# USB.net
KiCad netlist of a schematic drawn in Altium Designer
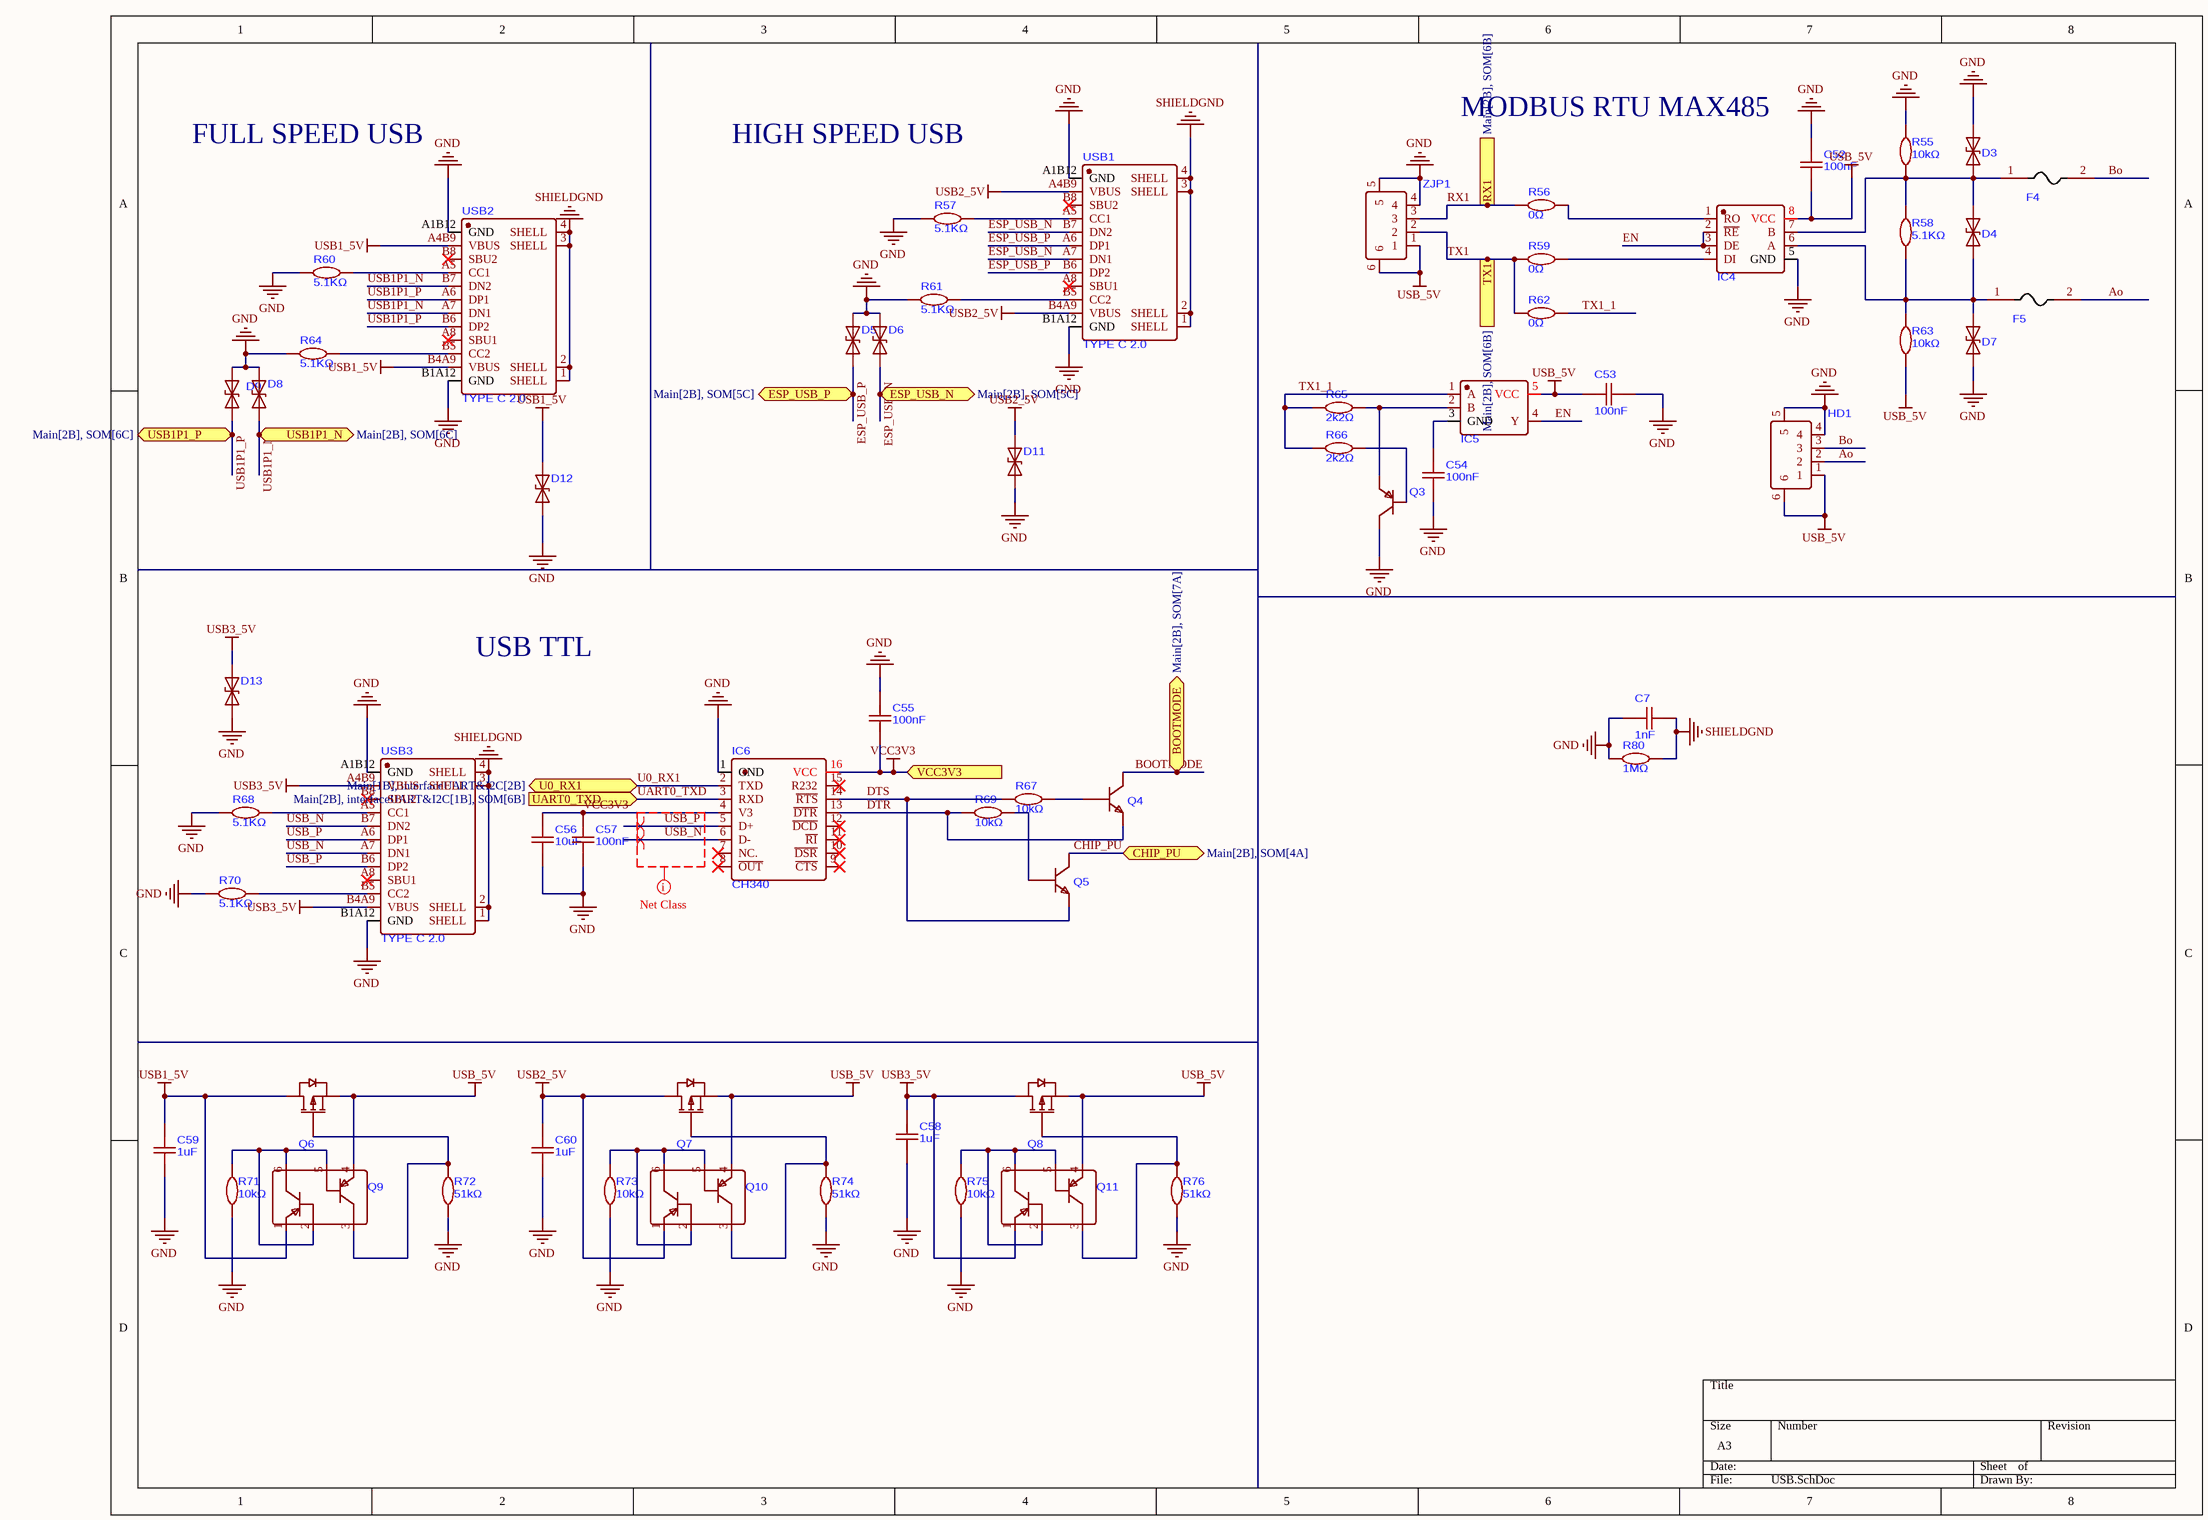
[diagram p0: USB.SchDoc]

(export (version "E")
  (design (tool "Eeschema 10.0.6"))
  (components
    (comp (ref "C7")
      (value "1nF")
      (footprint "C1808")
      (description "50V 1nF X7R ±10% 0603 Ceramic Capacitors ROHS")
      (libsource (lib "Schlib2") (part "CL10B102KB8NNNC"))
    )
    (comp (ref "C52")
      (value "100nF")
      (footprint "C0603")
      (description "50V 100nF X7R ±10% 0603 Ceramic Capacitors ROHS")
      (libsource (lib "Schlib2") (part "CC0603KRX7R9BB104"))
    )
    (comp (ref "C53")
      (value "100nF")
      (footprint "C0603")
      (description "50V 100nF X7R ±10% 0603 Ceramic Capacitors ROHS")
      (libsource (lib "Schlib2") (part "CC0603KRX7R9BB104"))
    )
    (comp (ref "C54")
      (value "100nF")
      (footprint "C0603")
      (description "50V 100nF X7R ±10% 0603 Ceramic Capacitors ROHS")
      (libsource (lib "Schlib2") (part "CC0603KRX7R9BB104"))
    )
    (comp (ref "C55")
      (value "100nF")
      (footprint "C0603")
      (description "50V 100nF X7R ±10% 0603 Ceramic Capacitors ROHS")
      (libsource (lib "Schlib2") (part "CC0603KRX7R9BB104"))
    )
    (comp (ref "C56")
      (value "10uF")
      (footprint "C0603")
      (description "25V 10uF X5R ±20% 0603 Ceramic Capacitors ROHS")
      (libsource (lib "Schlib2") (part "CL10A106MA8NRNC"))
    )
    (comp (ref "C57")
      (value "100nF")
      (footprint "C0603")
      (description "50V 100nF X7R ±10% 0603 Ceramic Capacitors ROHS")
      (libsource (lib "Schlib2") (part "CC0603KRX7R9BB104"))
    )
    (comp (ref "C58")
      (value "1uF")
      (footprint "C0603")
      (description "25V 1uF X7R ±10% 0603 Ceramic Capacitors ROHS")
      (libsource (lib "Schlib2") (part "CL10B105KA8NNNC"))
    )
    (comp (ref "C59")
      (value "1uF")
      (footprint "C0603")
      (description "25V 1uF X7R ±10% 0603 Ceramic Capacitors ROHS")
      (libsource (lib "Schlib2") (part "CL10B105KA8NNNC"))
    )
    (comp (ref "C60")
      (value "1uF")
      (footprint "C0603")
      (description "25V 1uF X7R ±10% 0603 Ceramic Capacitors ROHS")
      (libsource (lib "Schlib2") (part "CL10B105KA8NNNC"))
    )
    (comp (ref "D3")
      (value "TVS DIODE 5VWM 18.6VC SOD-523")
      (footprint "SOD-523_L1.2-W0.8-LS1.6-BI")
      (description "9.4A@8/20us 18.6V 7.8V 5V SOD-523 TVS Diodes RoHS")
      (libsource (lib "Schlib2") (part "LESD5D5.0CT1G"))
    )
    (comp (ref "D4")
      (value "TVS DIODE 5VWM 18.6VC SOD-523")
      (footprint "SOD-523_L1.2-W0.8-LS1.6-BI")
      (description "9.4A@8/20us 18.6V 7.8V 5V SOD-523 TVS Diodes RoHS")
      (libsource (lib "Schlib2") (part "LESD5D5.0CT1G"))
    )
    (comp (ref "D5")
      (value "TVS DIODE 5VWM 18.6VC SOD-523")
      (footprint "SOD-523_L1.2-W0.8-LS1.6-BI")
      (description "9.4A@8/20us 18.6V 7.8V 5V SOD-523 TVS Diodes RoHS")
      (libsource (lib "Schlib2") (part "LESD5D5.0CT1G"))
    )
    (comp (ref "D6")
      (value "TVS DIODE 5VWM 18.6VC SOD-523")
      (footprint "SOD-523_L1.2-W0.8-LS1.6-BI")
      (description "9.4A@8/20us 18.6V 7.8V 5V SOD-523 TVS Diodes RoHS")
      (libsource (lib "Schlib2") (part "LESD5D5.0CT1G"))
    )
    (comp (ref "D7")
      (value "TVS DIODE 5VWM 18.6VC SOD-523")
      (footprint "SOD-523_L1.2-W0.8-LS1.6-BI")
      (description "9.4A@8/20us 18.6V 7.8V 5V SOD-523 TVS Diodes RoHS")
      (libsource (lib "Schlib2") (part "LESD5D5.0CT1G"))
    )
    (comp (ref "D8")
      (value "TVS DIODE 5VWM 18.6VC SOD-523")
      (footprint "SOD-523_L1.2-W0.8-LS1.6-BI")
      (description "9.4A@8/20us 18.6V 7.8V 5V SOD-523 TVS Diodes RoHS")
      (libsource (lib "Schlib2") (part "LESD5D5.0CT1G"))
    )
    (comp (ref "D9")
      (value "TVS DIODE 5VWM 18.6VC SOD-523")
      (footprint "SOD-523_L1.2-W0.8-LS1.6-BI")
      (description "9.4A@8/20us 18.6V 7.8V 5V SOD-523 TVS Diodes RoHS")
      (libsource (lib "Schlib2") (part "LESD5D5.0CT1G"))
    )
    (comp (ref "D11")
      (value "TVS DIODE 5VWM 18.6VC SOD-523")
      (footprint "SOD-523_L1.2-W0.8-LS1.6-BI")
      (description "9.4A@8/20us 18.6V 7.8V 5V SOD-523 TVS Diodes RoHS")
      (libsource (lib "Schlib2") (part "LESD5D5.0CT1G"))
    )
    (comp (ref "D12")
      (value "TVS DIODE 5VWM 18.6VC SOD-523")
      (footprint "SOD-523_L1.2-W0.8-LS1.6-BI")
      (description "9.4A@8/20us 18.6V 7.8V 5V SOD-523 TVS Diodes RoHS")
      (libsource (lib "Schlib2") (part "LESD5D5.0CT1G"))
    )
    (comp (ref "D13")
      (value "TVS DIODE 5VWM 18.6VC SOD-523")
      (footprint "SOD-523_L1.2-W0.8-LS1.6-BI")
      (description "9.4A@8/20us 18.6V 7.8V 5V SOD-523 TVS Diodes RoHS")
      (libsource (lib "Schlib2") (part "LESD5D5.0CT1G"))
    )
    (comp (ref "F4")
      (value "PTC RESET FUSE 24V 100mA 0603")
      (footprint "F0603")
      (description "24V 100mA 40A 300mA 900mΩ 0603 PTC Resettable Fuses RoHS")
      (libsource (lib "Schlib2") (part "0603-010-24V"))
    )
    (comp (ref "F5")
      (value "PTC RESET FUSE 24V 100mA 0603")
      (footprint "F0603")
      (description "24V 100mA 40A 300mA 900mΩ 0603 PTC Resettable Fuses RoHS")
      (libsource (lib "Schlib2") (part "0603-010-24V"))
    )
    (comp (ref "HD1")
      (value "533980471")
      (footprint "CONN-SMD_4P-P1.25_XUNPU_WAFER-GH1.25-4PWB")
      (libsource (lib "Schlib2") (part "533980471"))
    )
    (comp (ref "IC4")
      (value "Low-Power, Slew-Rate-Limited RS-485/RS-422 Transceivers")
      (footprint "SOP-8_L4.9-W3.9-P1.27-LS6.0-BL")
      (description "Transceiver 4.75V~5.25V SOIC-8 Drivers, Receivers, Transceivers RoHS")
      (libsource (lib "Schlib2") (part "MAX485ESA+T_C41365333"))
    )
    (comp (ref "IC5")
      (value "SINGLE 2-INPUT NAND GATE WITH SCHMITT-TRIGGER INPUTS")
      (footprint "SOT-23-5_L3.0-W1.7-P0.95-LS2.8-BL")
      (description "5ns@5V,50pF 10uA 1.65V~5.5V NAND Gate SOT-23-5 Gates and Inverters RoHS")
      (libsource (lib "Schlib2") (part "TP74LVC1G132S5"))
    )
    (comp (ref "IC6")
      (value "CH340")
      (footprint "SOP-16_L10.0-W3.9-P1.27-LS6.0-BL")
      (description "Transceiver USB 2.0 SOP-16 Interface Controllers RoHS")
      (libsource (lib "Schlib2") (part "CH340C"))
    )
    (comp (ref "Q3")
      (value "TRANS PNP 25V 1.5A SOT-23")
      (footprint "SOT-23-3_L2.9-W1.3-P1.90-LS2.4-BR")
      (description "300mW 25V 1.5A PNP SOT-23 Single Bipolar Transistors RoHS")
      (libsource (lib "Schlib2") (part "SS8550_C7420371"))
    )
    (comp (ref "Q4")
      (value "TRANS NPN 25V 0.5A SOT-23")
      (footprint "SOT-23-3_L2.9-W1.3-P1.90-LS2.4-BR")
      (description "300mW 25V 500mA NPN SOT-23 Single Bipolar Transistors RoHS")
      (libsource (lib "Schlib2") (part "S8050_C2828466"))
    )
    (comp (ref "Q5")
      (value "TRANS NPN 25V 0.5A SOT-23")
      (footprint "SOT-23-3_L2.9-W1.3-P1.90-LS2.4-BR")
      (description "300mW 25V 500mA NPN SOT-23 Single Bipolar Transistors RoHS")
      (libsource (lib "Schlib2") (part "S8050_C2828466"))
    )
    (comp (ref "Q6")
      (value "MOSFET P-CH 30V 4.3A SOT-23")
      (footprint "2SOT-23-3_L2.9-W1.6-P1.90-LS2.8-BR")
      (description "30V 4.3A 48mΩ@10V 2.5V@250uA 1 P-Channel SOT-23 Single FETs, MOSFETs ROHS")
      (libsource (lib "Schlib2") (part "AO3407A"))
    )
    (comp (ref "Q7")
      (value "MOSFET P-CH 30V 4.3A SOT-23")
      (footprint "2SOT-23-3_L2.9-W1.6-P1.90-LS2.8-BR")
      (description "30V 4.3A 48mΩ@10V 2.5V@250uA 1 P-Channel SOT-23 Single FETs, MOSFETs ROHS")
      (libsource (lib "Schlib2") (part "AO3407A"))
    )
    (comp (ref "Q8")
      (value "MOSFET P-CH 30V 4.3A SOT-23")
      (footprint "2SOT-23-3_L2.9-W1.6-P1.90-LS2.8-BR")
      (description "30V 4.3A 48mΩ@10V 2.5V@250uA 1 P-Channel SOT-23 Single FETs, MOSFETs ROHS")
      (libsource (lib "Schlib2") (part "AO3407A"))
    )
    (comp (ref "Q9")
      (value "TRANS PNP 40V 200mA SOT-363")
      (footprint "SC-70-6_L2.2-W1.3-P0.65-LS2.1-TL")
      (description "40V 150mW 200mA PNP SOT-363 Single Bipolar Transistors RoHS")
      (libsource (lib "Schlib2") (part "LMBT3906DW1T1"))
    )
    (comp (ref "Q10")
      (value "TRANS PNP 40V 200mA SOT-363")
      (footprint "SC-70-6_L2.2-W1.3-P0.65-LS2.1-TL")
      (description "40V 150mW 200mA PNP SOT-363 Single Bipolar Transistors RoHS")
      (libsource (lib "Schlib2") (part "LMBT3906DW1T1"))
    )
    (comp (ref "Q11")
      (value "TRANS PNP 40V 200mA SOT-363")
      (footprint "SC-70-6_L2.2-W1.3-P0.65-LS2.1-TL")
      (description "40V 150mW 200mA PNP SOT-363 Single Bipolar Transistors RoHS")
      (libsource (lib "Schlib2") (part "LMBT3906DW1T1"))
    )
    (comp (ref "R55")
      (value "10kΩ")
      (footprint "R0603")
      (description "100mW 10kΩ 75V ±100ppm/℃ Thick Film Resistor ±1% 0603 Chip Resistor - Surface Mount ROHS")
      (libsource (lib "Schlib2") (part "RC0603FR-0710KL"))
    )
    (comp (ref "R56")
      (value "0Ω")
      (footprint "R0603")
      (description "100mW 0Ω 75V Thick Film Resistor ±5% 0603 Chip Resistor - Surface Mount RoHS")
      (libsource (lib "Schlib2") (part "RC0603JR-070RL"))
    )
    (comp (ref "R57")
      (value "5.1KΩ")
      (footprint "R0603")
      (description "100mW 5.1kΩ 75V ±100ppm/℃ Thick Film Resistor ±1% 0603 Chip Resistor - Surface Mount RoHS")
      (libsource (lib "Schlib2") (part "FRC0603F5101TS"))
    )
    (comp (ref "R58")
      (value "5.1KΩ")
      (footprint "R0603")
      (description "100mW 5.1kΩ 75V ±100ppm/℃ Thick Film Resistor ±1% 0603 Chip Resistor - Surface Mount RoHS")
      (libsource (lib "Schlib2") (part "FRC0603F5101TS"))
    )
    (comp (ref "R59")
      (value "0Ω")
      (footprint "R0603")
      (description "100mW 0Ω 75V Thick Film Resistor ±5% 0603 Chip Resistor - Surface Mount RoHS")
      (libsource (lib "Schlib2") (part "RC0603JR-070RL"))
    )
    (comp (ref "R60")
      (value "5.1KΩ")
      (footprint "R0603")
      (description "100mW 5.1kΩ 75V ±100ppm/℃ Thick Film Resistor ±1% 0603 Chip Resistor - Surface Mount RoHS")
      (libsource (lib "Schlib2") (part "FRC0603F5101TS"))
    )
    (comp (ref "R61")
      (value "5.1KΩ")
      (footprint "R0603")
      (description "100mW 5.1kΩ 75V ±100ppm/℃ Thick Film Resistor ±1% 0603 Chip Resistor - Surface Mount RoHS")
      (libsource (lib "Schlib2") (part "FRC0603F5101TS"))
    )
    (comp (ref "R62")
      (value "0Ω")
      (footprint "R0603")
      (description "100mW 0Ω 75V Thick Film Resistor ±5% 0603 Chip Resistor - Surface Mount RoHS")
      (libsource (lib "Schlib2") (part "RC0603JR-070RL"))
    )
    (comp (ref "R63")
      (value "10kΩ")
      (footprint "R0603")
      (description "100mW 10kΩ 75V ±100ppm/℃ Thick Film Resistor ±1% 0603 Chip Resistor - Surface Mount ROHS")
      (libsource (lib "Schlib2") (part "RC0603FR-0710KL"))
    )
    (comp (ref "R64")
      (value "5.1KΩ")
      (footprint "R0603")
      (description "100mW 5.1kΩ 75V ±100ppm/℃ Thick Film Resistor ±1% 0603 Chip Resistor - Surface Mount RoHS")
      (libsource (lib "Schlib2") (part "FRC0603F5101TS"))
    )
    (comp (ref "R65")
      (value "2k2Ω")
      (footprint "R0603")
      (description "100mW 2.2kΩ 75V ±100ppm/℃ Thick Film Resistor ±1% 0603 Chip Resistor - Surface Mount RoHS")
      (libsource (lib "Schlib2") (part "RC0603FR-072K2L"))
    )
    (comp (ref "R66")
      (value "2k2Ω")
      (footprint "R0603")
      (description "100mW 2.2kΩ 75V ±100ppm/℃ Thick Film Resistor ±1% 0603 Chip Resistor - Surface Mount RoHS")
      (libsource (lib "Schlib2") (part "RC0603FR-072K2L"))
    )
    (comp (ref "R67")
      (value "10kΩ")
      (footprint "R0603")
      (description "100mW 10kΩ 75V ±100ppm/℃ Thick Film Resistor ±1% 0603 Chip Resistor - Surface Mount ROHS")
      (libsource (lib "Schlib2") (part "RC0603FR-0710KL"))
    )
    (comp (ref "R68")
      (value "5.1KΩ")
      (footprint "R0603")
      (description "100mW 5.1kΩ 75V ±100ppm/℃ Thick Film Resistor ±1% 0603 Chip Resistor - Surface Mount RoHS")
      (libsource (lib "Schlib2") (part "FRC0603F5101TS"))
    )
    (comp (ref "R69")
      (value "10kΩ")
      (footprint "R0603")
      (description "100mW 10kΩ 75V ±100ppm/℃ Thick Film Resistor ±1% 0603 Chip Resistor - Surface Mount ROHS")
      (libsource (lib "Schlib2") (part "RC0603FR-0710KL"))
    )
    (comp (ref "R70")
      (value "5.1KΩ")
      (footprint "R0603")
      (description "100mW 5.1kΩ 75V ±100ppm/℃ Thick Film Resistor ±1% 0603 Chip Resistor - Surface Mount RoHS")
      (libsource (lib "Schlib2") (part "FRC0603F5101TS"))
    )
    (comp (ref "R71")
      (value "10kΩ")
      (footprint "R0603")
      (description "100mW 10kΩ 75V ±100ppm/℃ Thick Film Resistor ±1% 0603 Chip Resistor - Surface Mount ROHS")
      (libsource (lib "Schlib2") (part "RC0603FR-0710KL"))
    )
    (comp (ref "R72")
      (value "51kΩ")
      (footprint "R0603")
      (description "100mW 51kΩ 75V ±100ppm/℃ Thick Film Resistor ±1% 0603 Chip Resistor - Surface Mount RoHS")
      (libsource (lib "Schlib2") (part "RC0603FR-07100KL_1RC0603FR-0751KL"))
    )
    (comp (ref "R73")
      (value "10kΩ")
      (footprint "R0603")
      (description "100mW 10kΩ 75V ±100ppm/℃ Thick Film Resistor ±1% 0603 Chip Resistor - Surface Mount ROHS")
      (libsource (lib "Schlib2") (part "RC0603FR-0710KL"))
    )
    (comp (ref "R74")
      (value "51kΩ")
      (footprint "R0603")
      (description "100mW 51kΩ 75V ±100ppm/℃ Thick Film Resistor ±1% 0603 Chip Resistor - Surface Mount RoHS")
      (libsource (lib "Schlib2") (part "RC0603FR-07100KL_1RC0603FR-0751KL"))
    )
    (comp (ref "R75")
      (value "10kΩ")
      (footprint "R0603")
      (description "100mW 10kΩ 75V ±100ppm/℃ Thick Film Resistor ±1% 0603 Chip Resistor - Surface Mount ROHS")
      (libsource (lib "Schlib2") (part "RC0603FR-0710KL"))
    )
    (comp (ref "R76")
      (value "51kΩ")
      (footprint "R0603")
      (description "100mW 51kΩ 75V ±100ppm/℃ Thick Film Resistor ±1% 0603 Chip Resistor - Surface Mount RoHS")
      (libsource (lib "Schlib2") (part "RC0603FR-07100KL_1RC0603FR-0751KL"))
    )
    (comp (ref "R80")
      (value "1MΩ")
      (footprint "R2010")
      (description "100mW 1MΩ 75V Thick Film Resistor ±100ppm/℃ ±1% 0603 Chip Resistor - Surface Mount RoHS")
      (libsource (lib "Schlib2") (part "RC0603FR-071ML"))
    )
    (comp (ref "USB1")
      (value "TYPE C 2.0")
      (footprint "USB-C-SMD_G-SWITCH_GT-USB-7010ASV")
      (description "USB 2.0 1 16P -40℃~+85℃ Type-C SMD USB, DVI, HDMI Connector Assemblies RoHS")
      (libsource (lib "Schlib2") (part "GT-USB-7010ASV"))
    )
    (comp (ref "USB2")
      (value "TYPE C 2.0")
      (footprint "USB-C-SMD_G-SWITCH_GT-USB-7010ASV")
      (description "USB 2.0 1 16P -40℃~+85℃ Type-C SMD USB, DVI, HDMI Connector Assemblies RoHS")
      (libsource (lib "Schlib2") (part "GT-USB-7010ASV"))
    )
    (comp (ref "USB3")
      (value "TYPE C 2.0")
      (footprint "USB-C-SMD_G-SWITCH_GT-USB-7010ASV")
      (description "USB 2.0 1 16P -40℃~+85℃ Type-C SMD USB, DVI, HDMI Connector Assemblies RoHS")
      (libsource (lib "Schlib2") (part "GT-USB-7010ASV"))
    )
    (comp (ref "ZJP1")
      (value "533980471")
      (footprint "CONN-SMD_4P-P1.25_XUNPU_WAFER-GH1.25-4PWB")
      (libsource (lib "Schlib2") (part "533980471"))
    )
  )
  (nets
    (net (code "1") (name "/Ao") (class "Default")
      (node (ref "F5") (pin "2") (pinfunction "2_2") (pintype "passive"))
      (node (ref "HD1") (pin "2") (pinfunction "2_2") (pintype "passive"))
    )
    (net (code "2") (name "/BOOTMODE") (class "Default")
      (node (ref "Q4") (pin "3") (pinfunction "C_3") (pintype "passive"))
    )
    (net (code "3") (name "/Bo") (class "Default")
      (node (ref "F4") (pin "2") (pinfunction "2_2") (pintype "passive"))
      (node (ref "HD1") (pin "3") (pinfunction "3_3") (pintype "passive"))
    )
    (net (code "4") (name "/CHIP_PU") (class "Default")
      (node (ref "Q5") (pin "3") (pinfunction "C_3") (pintype "passive"))
    )
    (net (code "5") (name "/DTR") (class "Default")
      (node (ref "IC6") (pin "13") (pinfunction "~{DTR}_13") (pintype "passive"))
      (node (ref "Q4") (pin "2") (pinfunction "E_2") (pintype "passive"))
      (node (ref "R69") (pin "1") (pinfunction "1_1") (pintype "passive"))
    )
    (net (code "6") (name "/DTS") (class "Default")
      (node (ref "IC6") (pin "14") (pinfunction "~{RTS}_14") (pintype "passive"))
      (node (ref "Q5") (pin "2") (pinfunction "E_2") (pintype "passive"))
      (node (ref "R67") (pin "1") (pinfunction "1_1") (pintype "passive"))
    )
    (net (code "7") (name "/EN") (class "Default")
      (node (ref "IC4") (pin "2") (pinfunction "~{RE}_2") (pintype "passive"))
      (node (ref "IC4") (pin "3") (pinfunction "DE_3") (pintype "passive"))
      (node (ref "IC5") (pin "4") (pinfunction "Y_4") (pintype "passive"))
    )
    (net (code "8") (name "/ESP_USB_N") (class "Default")
      (node (ref "D6") (pin "1") (pinfunction "K_1") (pintype "passive"))
      (node (ref "USB1") (pin "A7") (pinfunction "DN1_A7") (pintype "passive"))
      (node (ref "USB1") (pin "B7") (pinfunction "DN2_B7") (pintype "passive"))
    )
    (net (code "9") (name "/ESP_USB_P") (class "Default")
      (node (ref "D5") (pin "1") (pinfunction "K_1") (pintype "passive"))
      (node (ref "USB1") (pin "A6") (pinfunction "DP1_A6") (pintype "passive"))
      (node (ref "USB1") (pin "B6") (pinfunction "DP2_B6") (pintype "passive"))
    )
    (net (code "10") (name "/RX1") (class "Default")
      (node (ref "R56") (pin "1") (pinfunction "1_1") (pintype "passive"))
      (node (ref "ZJP1") (pin "3") (pinfunction "3_3") (pintype "passive"))
    )
    (net (code "11") (name "/TX1") (class "Default")
      (node (ref "R59") (pin "1") (pinfunction "1_1") (pintype "passive"))
      (node (ref "R62") (pin "1") (pinfunction "1_1") (pintype "passive"))
      (node (ref "ZJP1") (pin "2") (pinfunction "2_2") (pintype "passive"))
    )
    (net (code "12") (name "/TX1_1") (class "Default")
      (node (ref "IC5") (pin "1") (pinfunction "A_1") (pintype "passive"))
      (node (ref "R62") (pin "2") (pinfunction "2_2") (pintype "passive"))
      (node (ref "R65") (pin "2") (pinfunction "2_2") (pintype "passive"))
      (node (ref "R66") (pin "1") (pinfunction "1_1") (pintype "passive"))
    )
    (net (code "13") (name "/U0_RX1") (class "Default")
      (node (ref "IC6") (pin "2") (pinfunction "TXD_2") (pintype "passive"))
    )
    (net (code "14") (name "/UART0_TXD") (class "Default")
      (node (ref "IC6") (pin "3") (pinfunction "RXD_3") (pintype "passive"))
    )
    (net (code "15") (name "/USB1P1_N") (class "Default")
      (node (ref "D8") (pin "1") (pinfunction "K_1") (pintype "passive"))
      (node (ref "USB2") (pin "A7") (pinfunction "DN1_A7") (pintype "passive"))
      (node (ref "USB2") (pin "B7") (pinfunction "DN2_B7") (pintype "passive"))
    )
    (net (code "16") (name "/USB1P1_P") (class "Default")
      (node (ref "D9") (pin "1") (pinfunction "K_1") (pintype "passive"))
      (node (ref "USB2") (pin "A6") (pinfunction "DP1_A6") (pintype "passive"))
      (node (ref "USB2") (pin "B6") (pinfunction "DP2_B6") (pintype "passive"))
    )
    (net (code "17") (name "/USB_N") (class "Default")
      (node (ref "IC6") (pin "6") (pinfunction "D-_6") (pintype "passive"))
      (node (ref "USB3") (pin "A7") (pinfunction "DN1_A7") (pintype "passive"))
      (node (ref "USB3") (pin "B7") (pinfunction "DN2_B7") (pintype "passive"))
    )
    (net (code "18") (name "/USB_P") (class "Default")
      (node (ref "IC6") (pin "5") (pinfunction "D+_5") (pintype "passive"))
      (node (ref "USB3") (pin "A6") (pinfunction "DP1_A6") (pintype "passive"))
      (node (ref "USB3") (pin "B6") (pinfunction "DP2_B6") (pintype "passive"))
    )
    (net (code "19") (name "GND") (class "Default")
      (node (ref "C52") (pin "2") (pinfunction "2_2") (pintype "passive"))
      (node (ref "C53") (pin "1") (pinfunction "1_1") (pintype "passive"))
      (node (ref "C54") (pin "1") (pinfunction "1_1") (pintype "passive"))
      (node (ref "C55") (pin "2") (pinfunction "2_2") (pintype "passive"))
      (node (ref "C56") (pin "1") (pinfunction "1_1") (pintype "passive"))
      (node (ref "C57") (pin "1") (pinfunction "1_1") (pintype "passive"))
      (node (ref "C58") (pin "1") (pinfunction "1_1") (pintype "passive"))
      (node (ref "C59") (pin "1") (pinfunction "1_1") (pintype "passive"))
      (node (ref "C60") (pin "1") (pinfunction "1_1") (pintype "passive"))
      (node (ref "C7") (pin "1") (pinfunction "1_1") (pintype "passive"))
      (node (ref "D11") (pin "1") (pinfunction "K_1") (pintype "passive"))
      (node (ref "D12") (pin "1") (pinfunction "K_1") (pintype "passive"))
      (node (ref "D13") (pin "1") (pinfunction "K_1") (pintype "passive"))
      (node (ref "D3") (pin "2") (pinfunction "A_2") (pintype "passive"))
      (node (ref "D5") (pin "2") (pinfunction "A_2") (pintype "passive"))
      (node (ref "D6") (pin "2") (pinfunction "A_2") (pintype "passive"))
      (node (ref "D7") (pin "1") (pinfunction "K_1") (pintype "passive"))
      (node (ref "D8") (pin "2") (pinfunction "A_2") (pintype "passive"))
      (node (ref "D9") (pin "2") (pinfunction "A_2") (pintype "passive"))
      (node (ref "HD1") (pin "4") (pinfunction "4_4") (pintype "passive"))
      (node (ref "HD1") (pin "5") (pinfunction "5_5") (pintype "passive"))
      (node (ref "IC4") (pin "5") (pinfunction "GND_5") (pintype "passive"))
      (node (ref "IC6") (pin "1") (pinfunction "GND_1") (pintype "passive"))
      (node (ref "Q3") (pin "3") (pinfunction "C_3") (pintype "passive"))
      (node (ref "R55") (pin "2") (pinfunction "2_2") (pintype "passive"))
      (node (ref "R57") (pin "1") (pinfunction "1_1") (pintype "passive"))
      (node (ref "R60") (pin "1") (pinfunction "1_1") (pintype "passive"))
      (node (ref "R61") (pin "1") (pinfunction "1_1") (pintype "passive"))
      (node (ref "R64") (pin "1") (pinfunction "1_1") (pintype "passive"))
      (node (ref "R68") (pin "1") (pinfunction "1_1") (pintype "passive"))
      (node (ref "R70") (pin "1") (pinfunction "1_1") (pintype "passive"))
      (node (ref "R71") (pin "1") (pinfunction "1_1") (pintype "passive"))
      (node (ref "R72") (pin "1") (pinfunction "1_1") (pintype "passive"))
      (node (ref "R73") (pin "1") (pinfunction "1_1") (pintype "passive"))
      (node (ref "R74") (pin "1") (pinfunction "1_1") (pintype "passive"))
      (node (ref "R75") (pin "1") (pinfunction "1_1") (pintype "passive"))
      (node (ref "R76") (pin "1") (pinfunction "1_1") (pintype "passive"))
      (node (ref "R80") (pin "1") (pinfunction "1_1") (pintype "passive"))
      (node (ref "USB1") (pin "A1B12") (pinfunction "GND_A1B12") (pintype "passive"))
      (node (ref "USB1") (pin "B1A12") (pinfunction "GND_B1A12") (pintype "passive"))
      (node (ref "USB2") (pin "A1B12") (pinfunction "GND_A1B12") (pintype "passive"))
      (node (ref "USB2") (pin "B1A12") (pinfunction "GND_B1A12") (pintype "passive"))
      (node (ref "USB3") (pin "A1B12") (pinfunction "GND_A1B12") (pintype "passive"))
      (node (ref "USB3") (pin "B1A12") (pinfunction "GND_B1A12") (pintype "passive"))
      (node (ref "ZJP1") (pin "4") (pinfunction "4_4") (pintype "passive"))
      (node (ref "ZJP1") (pin "5") (pinfunction "5_5") (pintype "passive"))
    )
    (net (code "20") (name "Net-(D3-K)") (class "Default")
      (node (ref "D3") (pin "1") (pinfunction "K_1") (pintype "passive"))
      (node (ref "D4") (pin "2") (pinfunction "A_2") (pintype "passive"))
      (node (ref "F4") (pin "1") (pinfunction "1_1") (pintype "passive"))
      (node (ref "IC4") (pin "7") (pinfunction "B_7") (pintype "passive"))
      (node (ref "R55") (pin "1") (pinfunction "1_1") (pintype "passive"))
      (node (ref "R58") (pin "2") (pinfunction "2_2") (pintype "passive"))
    )
    (net (code "21") (name "Net-(D4-K)") (class "Default")
      (node (ref "D4") (pin "1") (pinfunction "K_1") (pintype "passive"))
      (node (ref "D7") (pin "2") (pinfunction "A_2") (pintype "passive"))
      (node (ref "F5") (pin "1") (pinfunction "1_1") (pintype "passive"))
      (node (ref "IC4") (pin "6") (pinfunction "A_6") (pintype "passive"))
      (node (ref "R58") (pin "1") (pinfunction "1_1") (pintype "passive"))
      (node (ref "R63") (pin "2") (pinfunction "2_2") (pintype "passive"))
    )
    (net (code "22") (name "Net-(IC4-DI)") (class "Default")
      (node (ref "IC4") (pin "4") (pinfunction "DI_4") (pintype "passive"))
      (node (ref "R59") (pin "2") (pinfunction "2_2") (pintype "passive"))
    )
    (net (code "23") (name "Net-(IC4-RO)") (class "Default")
      (node (ref "IC4") (pin "1") (pinfunction "RO_1") (pintype "passive"))
      (node (ref "R56") (pin "2") (pinfunction "2_2") (pintype "passive"))
    )
    (net (code "24") (name "Net-(IC5-B)") (class "Default")
      (node (ref "IC5") (pin "2") (pinfunction "B_2") (pintype "passive"))
      (node (ref "Q3") (pin "2") (pinfunction "E_2") (pintype "passive"))
      (node (ref "R65") (pin "1") (pinfunction "1_1") (pintype "passive"))
    )
    (net (code "25") (name "Net-(IC5-GND)") (class "Default")
      (node (ref "C54") (pin "2") (pinfunction "2_2") (pintype "passive"))
      (node (ref "IC5") (pin "3") (pinfunction "GND_3") (pintype "passive"))
    )
    (net (code "26") (name "Net-(Q3-B)") (class "Default")
      (node (ref "Q3") (pin "1") (pinfunction "B_1") (pintype "passive"))
      (node (ref "R66") (pin "2") (pinfunction "2_2") (pintype "passive"))
    )
    (net (code "27") (name "Net-(Q4-B)") (class "Default")
      (node (ref "Q4") (pin "1") (pinfunction "B_1") (pintype "passive"))
      (node (ref "R67") (pin "2") (pinfunction "2_2") (pintype "passive"))
    )
    (net (code "28") (name "Net-(Q5-B)") (class "Default")
      (node (ref "Q5") (pin "1") (pinfunction "B_1") (pintype "passive"))
      (node (ref "R69") (pin "2") (pinfunction "2_2") (pintype "passive"))
    )
    (net (code "29") (name "Net-(Q6-G)") (class "Default")
      (node (ref "Q6") (pin "1") (pinfunction "G_1") (pintype "passive"))
      (node (ref "Q9") (pin "3") (pinfunction "C1_3") (pintype "passive"))
      (node (ref "R72") (pin "2") (pinfunction "2_2") (pintype "passive"))
    )
    (net (code "30") (name "Net-(Q9-B1)") (class "Default")
      (node (ref "Q9") (pin "2") (pinfunction "B2_2") (pintype "passive"))
      (node (ref "Q9") (pin "5") (pinfunction "B1_5") (pintype "passive"))
      (node (ref "Q9") (pin "6") (pinfunction "C2_6") (pintype "passive"))
      (node (ref "R71") (pin "2") (pinfunction "2_2") (pintype "passive"))
    )
    (net (code "31") (name "Net-(Q10-B1)") (class "Default")
      (node (ref "Q10") (pin "2") (pinfunction "B2_2") (pintype "passive"))
      (node (ref "Q10") (pin "5") (pinfunction "B1_5") (pintype "passive"))
      (node (ref "Q10") (pin "6") (pinfunction "C2_6") (pintype "passive"))
      (node (ref "R73") (pin "2") (pinfunction "2_2") (pintype "passive"))
    )
    (net (code "32") (name "Net-(Q10-C1)") (class "Default")
      (node (ref "Q10") (pin "3") (pinfunction "C1_3") (pintype "passive"))
      (node (ref "Q7") (pin "1") (pinfunction "G_1") (pintype "passive"))
      (node (ref "R74") (pin "2") (pinfunction "2_2") (pintype "passive"))
    )
    (net (code "33") (name "Net-(Q11-B1)") (class "Default")
      (node (ref "Q11") (pin "2") (pinfunction "B2_2") (pintype "passive"))
      (node (ref "Q11") (pin "5") (pinfunction "B1_5") (pintype "passive"))
      (node (ref "Q11") (pin "6") (pinfunction "C2_6") (pintype "passive"))
      (node (ref "R75") (pin "2") (pinfunction "2_2") (pintype "passive"))
    )
    (net (code "34") (name "Net-(Q11-C1)") (class "Default")
      (node (ref "Q11") (pin "3") (pinfunction "C1_3") (pintype "passive"))
      (node (ref "Q8") (pin "1") (pinfunction "G_1") (pintype "passive"))
      (node (ref "R76") (pin "2") (pinfunction "2_2") (pintype "passive"))
    )
    (net (code "35") (name "Net-(USB1-CC1)") (class "Default")
      (node (ref "R57") (pin "2") (pinfunction "2_2") (pintype "passive"))
      (node (ref "USB1") (pin "A5") (pinfunction "CC1_A5") (pintype "passive"))
    )
    (net (code "36") (name "Net-(USB1-CC2)") (class "Default")
      (node (ref "R61") (pin "2") (pinfunction "2_2") (pintype "passive"))
      (node (ref "USB1") (pin "B5") (pinfunction "CC2_B5") (pintype "passive"))
    )
    (net (code "37") (name "Net-(USB2-CC1)") (class "Default")
      (node (ref "R60") (pin "2") (pinfunction "2_2") (pintype "passive"))
      (node (ref "USB2") (pin "A5") (pinfunction "CC1_A5") (pintype "passive"))
    )
    (net (code "38") (name "Net-(USB2-CC2)") (class "Default")
      (node (ref "R64") (pin "2") (pinfunction "2_2") (pintype "passive"))
      (node (ref "USB2") (pin "B5") (pinfunction "CC2_B5") (pintype "passive"))
    )
    (net (code "39") (name "Net-(USB3-CC1)") (class "Default")
      (node (ref "R68") (pin "2") (pinfunction "2_2") (pintype "passive"))
      (node (ref "USB3") (pin "A5") (pinfunction "CC1_A5") (pintype "passive"))
    )
    (net (code "40") (name "Net-(USB3-CC2)") (class "Default")
      (node (ref "R70") (pin "2") (pinfunction "2_2") (pintype "passive"))
      (node (ref "USB3") (pin "B5") (pinfunction "CC2_B5") (pintype "passive"))
    )
    (net (code "41") (name "SHIELDGND") (class "Default")
      (node (ref "C7") (pin "2") (pinfunction "2_2") (pintype "passive"))
      (node (ref "R80") (pin "2") (pinfunction "2_2") (pintype "passive"))
      (node (ref "USB1") (pin "1") (pinfunction "SHELL_1") (pintype "passive"))
      (node (ref "USB1") (pin "2") (pinfunction "SHELL_2") (pintype "passive"))
      (node (ref "USB1") (pin "3") (pinfunction "SHELL_3") (pintype "passive"))
      (node (ref "USB1") (pin "4") (pinfunction "SHELL_4") (pintype "passive"))
      (node (ref "USB2") (pin "1") (pinfunction "SHELL_1") (pintype "passive"))
      (node (ref "USB2") (pin "2") (pinfunction "SHELL_2") (pintype "passive"))
      (node (ref "USB2") (pin "3") (pinfunction "SHELL_3") (pintype "passive"))
      (node (ref "USB2") (pin "4") (pinfunction "SHELL_4") (pintype "passive"))
      (node (ref "USB3") (pin "1") (pinfunction "SHELL_1") (pintype "passive"))
      (node (ref "USB3") (pin "2") (pinfunction "SHELL_2") (pintype "passive"))
      (node (ref "USB3") (pin "3") (pinfunction "SHELL_3") (pintype "passive"))
      (node (ref "USB3") (pin "4") (pinfunction "SHELL_4") (pintype "passive"))
    )
    (net (code "42") (name "USB1_5V") (class "Default")
      (node (ref "C59") (pin "2") (pinfunction "2_2") (pintype "passive"))
      (node (ref "D12") (pin "2") (pinfunction "A_2") (pintype "passive"))
      (node (ref "Q6") (pin "3") (pinfunction "D_3") (pintype "passive"))
      (node (ref "Q9") (pin "1") (pinfunction "E2_1") (pintype "passive"))
      (node (ref "USB2") (pin "A4B9") (pinfunction "VBUS_A4B9") (pintype "passive"))
      (node (ref "USB2") (pin "B4A9") (pinfunction "VBUS_B4A9") (pintype "passive"))
    )
    (net (code "43") (name "USB2_5V") (class "Default")
      (node (ref "C60") (pin "2") (pinfunction "2_2") (pintype "passive"))
      (node (ref "D11") (pin "2") (pinfunction "A_2") (pintype "passive"))
      (node (ref "Q10") (pin "1") (pinfunction "E2_1") (pintype "passive"))
      (node (ref "Q7") (pin "3") (pinfunction "D_3") (pintype "passive"))
      (node (ref "USB1") (pin "A4B9") (pinfunction "VBUS_A4B9") (pintype "passive"))
      (node (ref "USB1") (pin "B4A9") (pinfunction "VBUS_B4A9") (pintype "passive"))
    )
    (net (code "44") (name "USB3_5V") (class "Default")
      (node (ref "C58") (pin "2") (pinfunction "2_2") (pintype "passive"))
      (node (ref "D13") (pin "2") (pinfunction "A_2") (pintype "passive"))
      (node (ref "Q11") (pin "1") (pinfunction "E2_1") (pintype "passive"))
      (node (ref "Q8") (pin "3") (pinfunction "D_3") (pintype "passive"))
      (node (ref "USB3") (pin "A4B9") (pinfunction "VBUS_A4B9") (pintype "passive"))
      (node (ref "USB3") (pin "B4A9") (pinfunction "VBUS_B4A9") (pintype "passive"))
    )
    (net (code "45") (name "USB_5V") (class "Default")
      (node (ref "C52") (pin "1") (pinfunction "1_1") (pintype "passive"))
      (node (ref "C53") (pin "2") (pinfunction "2_2") (pintype "passive"))
      (node (ref "HD1") (pin "1") (pinfunction "1_1") (pintype "passive"))
      (node (ref "HD1") (pin "6") (pinfunction "6_6") (pintype "passive"))
      (node (ref "IC4") (pin "8") (pinfunction "VCC_8") (pintype "passive"))
      (node (ref "IC5") (pin "5") (pinfunction "VCC_5") (pintype "passive"))
      (node (ref "Q10") (pin "4") (pinfunction "E1_4") (pintype "passive"))
      (node (ref "Q11") (pin "4") (pinfunction "E1_4") (pintype "passive"))
      (node (ref "Q6") (pin "2") (pinfunction "S_2") (pintype "passive"))
      (node (ref "Q7") (pin "2") (pinfunction "S_2") (pintype "passive"))
      (node (ref "Q8") (pin "2") (pinfunction "S_2") (pintype "passive"))
      (node (ref "Q9") (pin "4") (pinfunction "E1_4") (pintype "passive"))
      (node (ref "R63") (pin "1") (pinfunction "1_1") (pintype "passive"))
      (node (ref "ZJP1") (pin "1") (pinfunction "1_1") (pintype "passive"))
      (node (ref "ZJP1") (pin "6") (pinfunction "6_6") (pintype "passive"))
    )
    (net (code "46") (name "VCC3V3") (class "Default")
      (node (ref "C55") (pin "1") (pinfunction "1_1") (pintype "passive"))
      (node (ref "C56") (pin "2") (pinfunction "2_2") (pintype "passive"))
      (node (ref "C57") (pin "2") (pinfunction "2_2") (pintype "passive"))
      (node (ref "IC6") (pin "16") (pinfunction "VCC_16") (pintype "passive"))
      (node (ref "IC6") (pin "4") (pinfunction "V3_4") (pintype "passive"))
    )
    (net (code "47") (name "unconnected-(IC6-NC.-Pad7)") (class "Default")
      (node (ref "IC6") (pin "7") (pinfunction "NC._7") (pintype "passive+no_connect"))
    )
    (net (code "48") (name "unconnected-(IC6-R232-Pad15)") (class "Default")
      (node (ref "IC6") (pin "15") (pinfunction "R232_15") (pintype "passive+no_connect"))
    )
    (net (code "49") (name "unconnected-(IC6-~{CTS}-Pad9)") (class "Default")
      (node (ref "IC6") (pin "9") (pinfunction "~{CTS}_9") (pintype "passive+no_connect"))
    )
    (net (code "50") (name "unconnected-(IC6-~{DCD}-Pad12)") (class "Default")
      (node (ref "IC6") (pin "12") (pinfunction "~{DCD}_12") (pintype "passive+no_connect"))
    )
    (net (code "51") (name "unconnected-(IC6-~{DSR}-Pad10)") (class "Default")
      (node (ref "IC6") (pin "10") (pinfunction "~{DSR}_10") (pintype "passive+no_connect"))
    )
    (net (code "52") (name "unconnected-(IC6-~{OUT}-Pad8)") (class "Default")
      (node (ref "IC6") (pin "8") (pinfunction "~{OUT}_8") (pintype "passive+no_connect"))
    )
    (net (code "53") (name "unconnected-(IC6-~{RI}-Pad11)") (class "Default")
      (node (ref "IC6") (pin "11") (pinfunction "~{RI}_11") (pintype "passive+no_connect"))
    )
    (net (code "54") (name "unconnected-(USB1-SBU1-PadA8)") (class "Default")
      (node (ref "USB1") (pin "A8") (pinfunction "SBU1_A8") (pintype "passive+no_connect"))
    )
    (net (code "55") (name "unconnected-(USB1-SBU2-PadB8)") (class "Default")
      (node (ref "USB1") (pin "B8") (pinfunction "SBU2_B8") (pintype "passive+no_connect"))
    )
    (net (code "56") (name "unconnected-(USB2-SBU1-PadA8)") (class "Default")
      (node (ref "USB2") (pin "A8") (pinfunction "SBU1_A8") (pintype "passive+no_connect"))
    )
    (net (code "57") (name "unconnected-(USB2-SBU2-PadB8)") (class "Default")
      (node (ref "USB2") (pin "B8") (pinfunction "SBU2_B8") (pintype "passive+no_connect"))
    )
    (net (code "58") (name "unconnected-(USB3-SBU1-PadA8)") (class "Default")
      (node (ref "USB3") (pin "A8") (pinfunction "SBU1_A8") (pintype "passive+no_connect"))
    )
    (net (code "59") (name "unconnected-(USB3-SBU2-PadB8)") (class "Default")
      (node (ref "USB3") (pin "B8") (pinfunction "SBU2_B8") (pintype "passive+no_connect"))
    )
  )
)
